# Display.net
KiCad netlist of a schematic drawn in Altium Designer
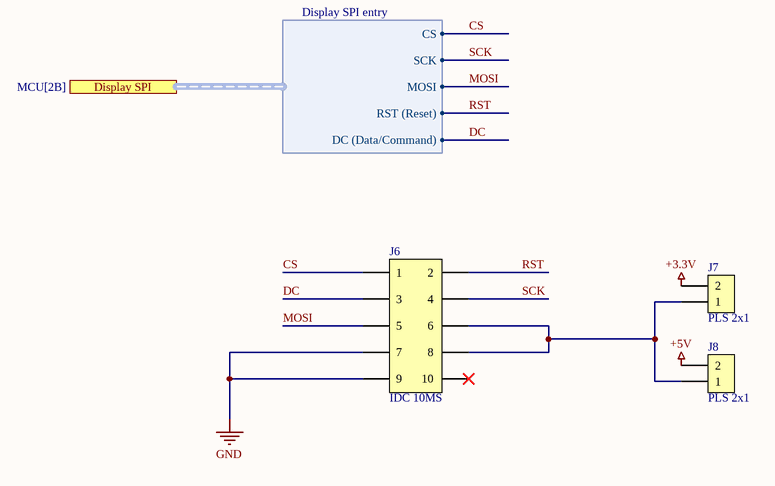
[diagram p0: Display.SchDoc]

(export (version "E")
  (design (tool "Eeschema 10.0.6"))
  (components
    (comp (ref "J6")
      (value "IDC 10MS")
      (footprint "IDC 10MS")
      (libsource (lib "Altium_Library") (part "Connector IDC 10MS"))
    )
    (comp (ref "J7")
      (value "PLS 2x1")
      (footprint "PLS 2X1")
      (libsource (lib "BRT_Components") (part "Conn 2 (PLS)"))
    )
    (comp (ref "J8")
      (value "PLS 2x1")
      (footprint "PLS 2X1")
      (libsource (lib "BRT_Components") (part "Conn 2 (PLS)"))
    )
  )
  (nets
    (net (code "4") (name "+3.3V") (class "Default")
      (node (ref "J7") (pin "2") (pinfunction "2_2") (pintype "passive"))
    )
    (net (code "5") (name "+5V") (class "Default")
      (node (ref "J8") (pin "2") (pinfunction "2_2") (pintype "passive"))
    )
    (net (code "6") (name "/CS") (class "Default")
      (node (ref "J6") (pin "1") (pinfunction "1_1") (pintype "passive"))
    )
    (net (code "7") (name "/DC") (class "Default")
      (node (ref "J6") (pin "3") (pinfunction "3_3") (pintype "passive"))
    )
    (net (code "8") (name "/MOSI") (class "Default")
      (node (ref "J6") (pin "5") (pinfunction "5_5") (pintype "passive"))
    )
    (net (code "9") (name "/RST") (class "Default")
      (node (ref "J6") (pin "2") (pinfunction "2_2") (pintype "passive"))
    )
    (net (code "10") (name "/SCK") (class "Default")
      (node (ref "J6") (pin "4") (pinfunction "4_4") (pintype "passive"))
    )
    (net (code "12") (name "GND") (class "Default")
      (node (ref "J6") (pin "7") (pinfunction "7_7") (pintype "passive"))
      (node (ref "J6") (pin "9") (pinfunction "9_9") (pintype "passive"))
    )
    (net (code "13") (name "Net-(J6-Pad6)") (class "Default")
      (node (ref "J6") (pin "6") (pinfunction "6_6") (pintype "passive"))
      (node (ref "J6") (pin "8") (pinfunction "8_8") (pintype "passive"))
      (node (ref "J7") (pin "1") (pinfunction "1_1") (pintype "passive"))
      (node (ref "J8") (pin "1") (pinfunction "1_1") (pintype "passive"))
    )
    (net (code "14") (name "unconnected-(J6-Pad10)") (class "Default")
      (node (ref "J6") (pin "10") (pinfunction "10_10") (pintype "passive+no_connect"))
    )
  )
)
